# CPU.net
KiCad netlist of a schematic drawn in Altium Designer
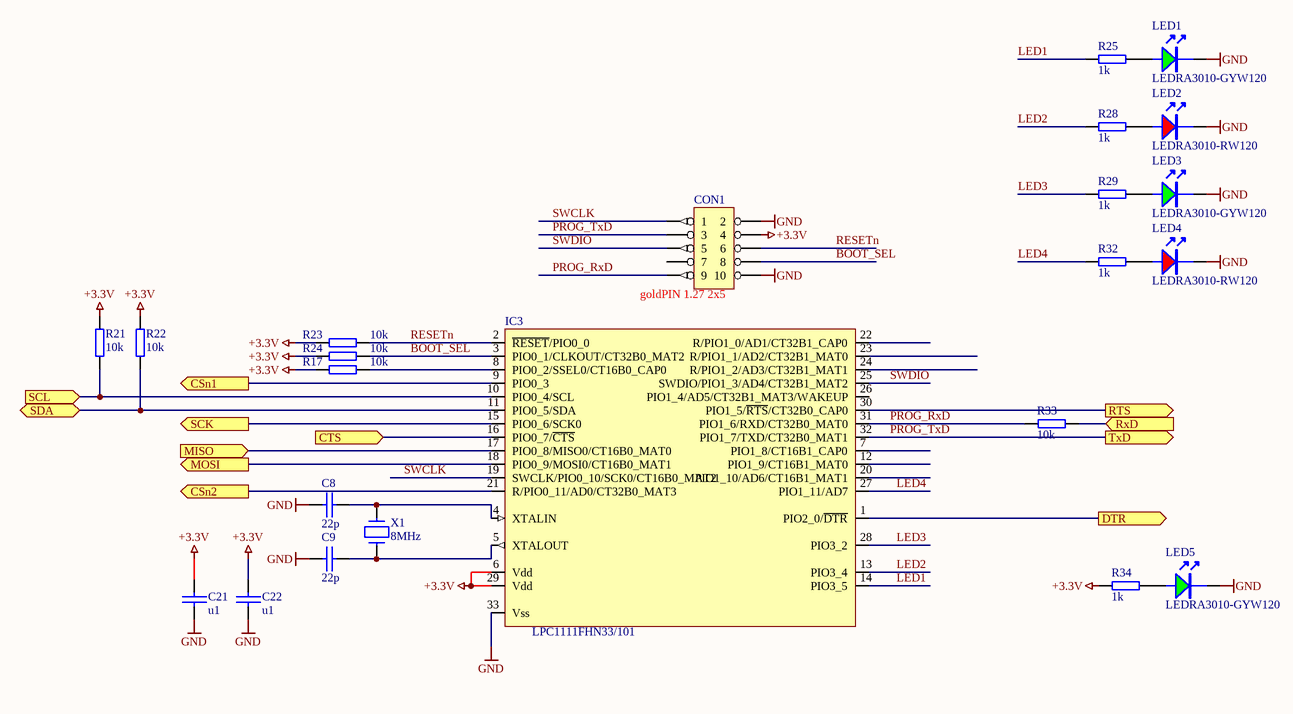
[diagram p0: CPU.SchDoc]

(export (version "E")
  (design (tool "Eeschema 10.0.6"))
  (components
    (comp (ref "C8")
      (value "22p")
      (footprint "0603C")
      (description "Capacitor SMD")
      (libsource (lib "LIBRARY_SCH") (part "CAP_SMD_0603"))
    )
    (comp (ref "C9")
      (value "22p")
      (footprint "0603C")
      (description "Capacitor SMD")
      (libsource (lib "LIBRARY_SCH") (part "CAP_SMD_0603"))
    )
    (comp (ref "C21")
      (value "u1")
      (footprint "0603")
      (description "Capacitor SMD")
      (libsource (lib "LIBRARY_SCH") (part "CAP_SMD"))
    )
    (comp (ref "C22")
      (value "u1")
      (footprint "0603")
      (description "Capacitor SMD")
      (libsource (lib "LIBRARY_SCH") (part "CAP_SMD"))
    )
    (comp (ref "CON1")
      (value "goldPIN 1.27 2x5")
      (footprint "CON_2x5_MINI")
      (libsource (lib "*") (part "HEADER 5X2"))
    )
    (comp (ref "IC3")
      (value "LPC1111FHN33/101")
      (footprint "HVQFN33_QFN127P600-8N")
      (libsource (lib "LIBRARY_SCH") (part "UPC_LPC1111"))
    )
    (comp (ref "LED1")
      (value "LEDRA3010-GYW120")
      (footprint "LED_KPA3010_G")
      (description "LED (Maritex)")
      (libsource (lib "LIBRARY_SCH") (part "LED_SMD_90deg_G"))
    )
    (comp (ref "LED2")
      (value "LEDRA3010-RW120")
      (footprint "LED_KPA3010_R")
      (description "LED (Maritex)")
      (libsource (lib "LIBRARY_SCH") (part "LED_SMD_90deg_R"))
    )
    (comp (ref "LED3")
      (value "LEDRA3010-GYW120")
      (footprint "LED_KPA3010_G")
      (description "LED (Maritex)")
      (libsource (lib "LIBRARY_SCH") (part "LED_SMD_90deg_G"))
    )
    (comp (ref "LED4")
      (value "LEDRA3010-RW120")
      (footprint "LED_KPA3010_R")
      (description "LED (Maritex)")
      (libsource (lib "LIBRARY_SCH") (part "LED_SMD_90deg_R"))
    )
    (comp (ref "LED5")
      (value "LEDRA3010-GYW120")
      (footprint "LED_KPA3010_G")
      (description "LED (Maritex)")
      (libsource (lib "LIBRARY_SCH") (part "LED_SMD_90deg_G"))
    )
    (comp (ref "R17")
      (value "10k")
      (footprint "0603r")
      (description "SMD Resistor")
      (libsource (lib "LIBRARY_SCH") (part "RES_SMD"))
    )
    (comp (ref "R21")
      (value "10k")
      (footprint "0603R")
      (description "SMD Resistor")
      (libsource (lib "LIBRARY_SCH") (part "RES_0603"))
    )
    (comp (ref "R22")
      (value "10k")
      (footprint "0603R")
      (description "SMD Resistor")
      (libsource (lib "LIBRARY_SCH") (part "RES_0603"))
    )
    (comp (ref "R23")
      (value "10k")
      (footprint "0603r")
      (description "SMD Resistor")
      (libsource (lib "LIBRARY_SCH") (part "RES_SMD"))
    )
    (comp (ref "R24")
      (value "10k")
      (footprint "0603r")
      (description "SMD Resistor")
      (libsource (lib "LIBRARY_SCH") (part "RES_SMD"))
    )
    (comp (ref "R25")
      (value "1k")
      (footprint "0603r")
      (description "SMD Resistor")
      (libsource (lib "LIBRARY_SCH") (part "RES_SMD"))
    )
    (comp (ref "R28")
      (value "1k")
      (footprint "0603r")
      (description "SMD Resistor")
      (libsource (lib "LIBRARY_SCH") (part "RES_SMD"))
    )
    (comp (ref "R29")
      (value "1k")
      (footprint "0603r")
      (description "SMD Resistor")
      (libsource (lib "LIBRARY_SCH") (part "RES_SMD"))
    )
    (comp (ref "R32")
      (value "1k")
      (footprint "0603r")
      (description "SMD Resistor")
      (libsource (lib "LIBRARY_SCH") (part "RES_SMD"))
    )
    (comp (ref "R33")
      (value "10k")
      (footprint "0603r")
      (description "SMD Resistor")
      (libsource (lib "LIBRARY_SCH") (part "RES_SMD"))
    )
    (comp (ref "R34")
      (value "1k")
      (footprint "0603r")
      (description "SMD Resistor")
      (libsource (lib "LIBRARY_SCH") (part "RES_SMD"))
    )
    (comp (ref "X1")
      (value "8MHz")
      (footprint "HC-49SM")
      (description "Crystal oscillator")
      (libsource (lib "LIBRARY_SCH") (part "X_CRYSTAL"))
    )
  )
  (nets
    (net (code "1") (name "+3.3V") (class "Default")
      (node (ref "C21") (pin "1") (pinfunction "1_1") (pintype "passive"))
      (node (ref "C22") (pin "1") (pinfunction "1_1") (pintype "passive"))
      (node (ref "CON1") (pin "4") (pinfunction "4_4") (pintype "passive"))
      (node (ref "IC3") (pin "29") (pinfunction "Vdd_29") (pintype "power_in"))
      (node (ref "IC3") (pin "6") (pinfunction "Vdd_6") (pintype "power_in"))
      (node (ref "R17") (pin "2") (pinfunction "2_2") (pintype "passive"))
      (node (ref "R21") (pin "2") (pinfunction "2_2") (pintype "passive"))
      (node (ref "R22") (pin "2") (pinfunction "2_2") (pintype "passive"))
      (node (ref "R23") (pin "2") (pinfunction "2_2") (pintype "passive"))
      (node (ref "R24") (pin "2") (pinfunction "2_2") (pintype "passive"))
      (node (ref "R34") (pin "1") (pinfunction "1_1") (pintype "passive"))
    )
    (net (code "2") (name "/BOOT_SEL") (class "Default")
      (node (ref "CON1") (pin "8") (pinfunction "8_8") (pintype "passive"))
      (node (ref "IC3") (pin "3") (pinfunction "PIO0_1/CLKOUT/CT32B0_MAT2_3") (pintype "bidirectional"))
      (node (ref "R24") (pin "1") (pinfunction "1_1") (pintype "passive"))
    )
    (net (code "3") (name "/CSn1") (class "Default")
      (node (ref "IC3") (pin "9") (pinfunction "PIO0_3_9") (pintype "bidirectional"))
    )
    (net (code "4") (name "/CSn2") (class "Default")
      (node (ref "IC3") (pin "21") (pinfunction "R/PIO0_11/AD0/CT32B0_MAT3_21") (pintype "bidirectional"))
    )
    (net (code "5") (name "/CTS") (class "Default")
      (node (ref "IC3") (pin "16") (pinfunction "PIO0_7/~{CTS}_16") (pintype "bidirectional"))
    )
    (net (code "6") (name "/DTR") (class "Default")
      (node (ref "IC3") (pin "1") (pinfunction "PIO2_0/~{DTR}_1") (pintype "bidirectional"))
    )
    (net (code "7") (name "/LED1") (class "Default")
      (node (ref "IC3") (pin "14") (pinfunction "PIO3_5_14") (pintype "bidirectional"))
      (node (ref "R25") (pin "1") (pinfunction "1_1") (pintype "passive"))
    )
    (net (code "8") (name "/LED2") (class "Default")
      (node (ref "IC3") (pin "13") (pinfunction "PIO3_4_13") (pintype "bidirectional"))
      (node (ref "R28") (pin "1") (pinfunction "1_1") (pintype "passive"))
    )
    (net (code "9") (name "/LED3") (class "Default")
      (node (ref "IC3") (pin "28") (pinfunction "PIO3_2_28") (pintype "bidirectional"))
      (node (ref "R29") (pin "1") (pinfunction "1_1") (pintype "passive"))
    )
    (net (code "10") (name "/LED4") (class "Default")
      (node (ref "IC3") (pin "27") (pinfunction "PIO1_11/AD7_27") (pintype "bidirectional"))
      (node (ref "R32") (pin "1") (pinfunction "1_1") (pintype "passive"))
    )
    (net (code "11") (name "/MISO") (class "Default")
      (node (ref "IC3") (pin "17") (pinfunction "PIO0_8/MISO0/CT16B0_MAT0_17") (pintype "bidirectional"))
    )
    (net (code "12") (name "/MOSI") (class "Default")
      (node (ref "IC3") (pin "18") (pinfunction "PIO0_9/MOSI0/CT16B0_MAT1_18") (pintype "bidirectional"))
    )
    (net (code "13") (name "/PROG_RxD") (class "Default")
      (node (ref "CON1") (pin "9") (pinfunction "9_9") (pintype "output"))
      (node (ref "IC3") (pin "31") (pinfunction "PIO1_6/RXD/CT32B0_MAT0_31") (pintype "bidirectional"))
      (node (ref "R33") (pin "1") (pinfunction "1_1") (pintype "passive"))
    )
    (net (code "14") (name "/PROG_TxD") (class "Default")
      (node (ref "CON1") (pin "3") (pinfunction "3_3") (pintype "passive"))
      (node (ref "IC3") (pin "32") (pinfunction "PIO1_7/TXD/CT32B0_MAT1_32") (pintype "bidirectional"))
    )
    (net (code "15") (name "/RESETn") (class "Default")
      (node (ref "CON1") (pin "6") (pinfunction "6_6") (pintype "passive"))
      (node (ref "IC3") (pin "2") (pinfunction "~{RESET}/PIO0_0_2") (pintype "bidirectional"))
      (node (ref "R23") (pin "1") (pinfunction "1_1") (pintype "passive"))
    )
    (net (code "16") (name "/RTS") (class "Default")
      (node (ref "IC3") (pin "30") (pinfunction "PIO1_5/~{RTS}/CT32B0_CAP0_30") (pintype "bidirectional"))
    )
    (net (code "17") (name "/RxD") (class "Default")
      (node (ref "R33") (pin "2") (pinfunction "2_2") (pintype "passive"))
    )
    (net (code "18") (name "/SCK") (class "Default")
      (node (ref "IC3") (pin "15") (pinfunction "PIO0_6/SCK0_15") (pintype "bidirectional"))
    )
    (net (code "19") (name "/SCL") (class "Default")
      (node (ref "IC3") (pin "10") (pinfunction "PIO0_4/SCL_10") (pintype "bidirectional"))
      (node (ref "R21") (pin "1") (pinfunction "1_1") (pintype "passive"))
    )
    (net (code "20") (name "/SDA") (class "Default")
      (node (ref "IC3") (pin "11") (pinfunction "PIO0_5/SDA_11") (pintype "bidirectional"))
      (node (ref "R22") (pin "1") (pinfunction "1_1") (pintype "passive"))
    )
    (net (code "21") (name "/SWCLK") (class "Default")
      (node (ref "CON1") (pin "1") (pinfunction "1_1") (pintype "output"))
      (node (ref "IC3") (pin "19") (pinfunction "SWCLK/PIO0_10/SCK0/CT16B0_MAT2_19") (pintype "bidirectional"))
    )
    (net (code "22") (name "/SWDIO") (class "Default")
      (node (ref "CON1") (pin "5") (pinfunction "5_5") (pintype "output"))
      (node (ref "IC3") (pin "25") (pinfunction "SWDIO/PIO1_3/AD4/CT32B1_MAT2_25") (pintype "bidirectional"))
    )
    (net (code "23") (name "GND") (class "Default")
      (node (ref "C21") (pin "2") (pinfunction "2_2") (pintype "passive"))
      (node (ref "C22") (pin "2") (pinfunction "2_2") (pintype "passive"))
      (node (ref "C8") (pin "1") (pinfunction "1_1") (pintype "passive"))
      (node (ref "C9") (pin "1") (pinfunction "1_1") (pintype "passive"))
      (node (ref "CON1") (pin "10") (pinfunction "10_10") (pintype "passive"))
      (node (ref "CON1") (pin "2") (pinfunction "2_2") (pintype "passive"))
      (node (ref "IC3") (pin "33") (pinfunction "Vss_33") (pintype "power_in"))
      (node (ref "LED1") (pin "K") (pinfunction "K_K") (pintype "passive"))
      (node (ref "LED2") (pin "K") (pinfunction "K_K") (pintype "passive"))
      (node (ref "LED3") (pin "K") (pinfunction "K_K") (pintype "passive"))
      (node (ref "LED4") (pin "K") (pinfunction "K_K") (pintype "passive"))
      (node (ref "LED5") (pin "K") (pinfunction "K_K") (pintype "passive"))
    )
    (net (code "24") (name "Net-(IC3-PIO0_2{slash}SSEL0{slash}CT16B0_CAP0)") (class "Default")
      (node (ref "IC3") (pin "8") (pinfunction "PIO0_2/SSEL0/CT16B0_CAP0_8") (pintype "bidirectional"))
      (node (ref "R17") (pin "1") (pinfunction "1_1") (pintype "passive"))
    )
    (net (code "25") (name "Net-(IC3-XTALIN)") (class "Default")
      (node (ref "C8") (pin "2") (pinfunction "2_2") (pintype "passive"))
      (node (ref "IC3") (pin "4") (pinfunction "XTALIN_4") (pintype "input"))
      (node (ref "X1") (pin "2") (pinfunction "2_2") (pintype "passive"))
    )
    (net (code "26") (name "Net-(IC3-XTALOUT)") (class "Default")
      (node (ref "C9") (pin "2") (pinfunction "2_2") (pintype "passive"))
      (node (ref "IC3") (pin "5") (pinfunction "XTALOUT_5") (pintype "output"))
      (node (ref "X1") (pin "1") (pinfunction "1_1") (pintype "passive"))
    )
    (net (code "27") (name "Net-(LED1-PadA)") (class "Default")
      (node (ref "LED1") (pin "A") (pinfunction "A_A") (pintype "passive"))
      (node (ref "R25") (pin "2") (pinfunction "2_2") (pintype "passive"))
    )
    (net (code "28") (name "Net-(LED2-PadA)") (class "Default")
      (node (ref "LED2") (pin "A") (pinfunction "A_A") (pintype "passive"))
      (node (ref "R28") (pin "2") (pinfunction "2_2") (pintype "passive"))
    )
    (net (code "29") (name "Net-(LED3-PadA)") (class "Default")
      (node (ref "LED3") (pin "A") (pinfunction "A_A") (pintype "passive"))
      (node (ref "R29") (pin "2") (pinfunction "2_2") (pintype "passive"))
    )
    (net (code "30") (name "Net-(LED4-PadA)") (class "Default")
      (node (ref "LED4") (pin "A") (pinfunction "A_A") (pintype "passive"))
      (node (ref "R32") (pin "2") (pinfunction "2_2") (pintype "passive"))
    )
    (net (code "31") (name "Net-(LED5-PadA)") (class "Default")
      (node (ref "LED5") (pin "A") (pinfunction "A_A") (pintype "passive"))
      (node (ref "R34") (pin "2") (pinfunction "2_2") (pintype "passive"))
    )
    (net (code "32") (name "unconnected-(CON1-Pad7)") (class "Default")
      (node (ref "CON1") (pin "7") (pinfunction "7_7") (pintype "passive"))
    )
    (net (code "33") (name "unconnected-(IC3-PIO1_4{slash}AD5{slash}CT32B1_MAT3{slash}WAKEUP-Pad26)") (class "Default")
      (node (ref "IC3") (pin "26") (pinfunction "PIO1_4/AD5/CT32B1_MAT3/WAKEUP_26") (pintype "bidirectional"))
    )
    (net (code "34") (name "unconnected-(IC3-PIO1_8{slash}CT16B1_CAP0-Pad7)") (class "Default")
      (node (ref "IC3") (pin "7") (pinfunction "PIO1_8/CT16B1_CAP0_7") (pintype "bidirectional"))
    )
    (net (code "35") (name "unconnected-(IC3-PIO1_9{slash}CT16B1_MAT0-Pad12)") (class "Default")
      (node (ref "IC3") (pin "12") (pinfunction "PIO1_9/CT16B1_MAT0_12") (pintype "bidirectional"))
    )
    (net (code "36") (name "unconnected-(IC3-PIO1_10{slash}AD6{slash}CT16B1_MAT1-Pad20)") (class "Default")
      (node (ref "IC3") (pin "20") (pinfunction "PIO1_10/AD6/CT16B1_MAT1_20") (pintype "bidirectional"))
    )
    (net (code "37") (name "unconnected-(IC3-R{slash}PIO1_0{slash}AD1{slash}CT32B1_CAP0-Pad22)") (class "Default")
      (node (ref "IC3") (pin "22") (pinfunction "R/PIO1_0/AD1/CT32B1_CAP0_22") (pintype "bidirectional"))
    )
    (net (code "38") (name "unconnected-(IC3-R{slash}PIO1_1{slash}AD2{slash}CT32B1_MAT0-Pad23)") (class "Default")
      (node (ref "IC3") (pin "23") (pinfunction "R/PIO1_1/AD2/CT32B1_MAT0_23") (pintype "bidirectional"))
    )
    (net (code "39") (name "unconnected-(IC3-R{slash}PIO1_2{slash}AD3{slash}CT32B1_MAT1-Pad24)") (class "Default")
      (node (ref "IC3") (pin "24") (pinfunction "R/PIO1_2/AD3/CT32B1_MAT1_24") (pintype "bidirectional"))
    )
  )
)
